# Sensor_Schematic.net
KiCad netlist of a schematic drawn in Altium Designer
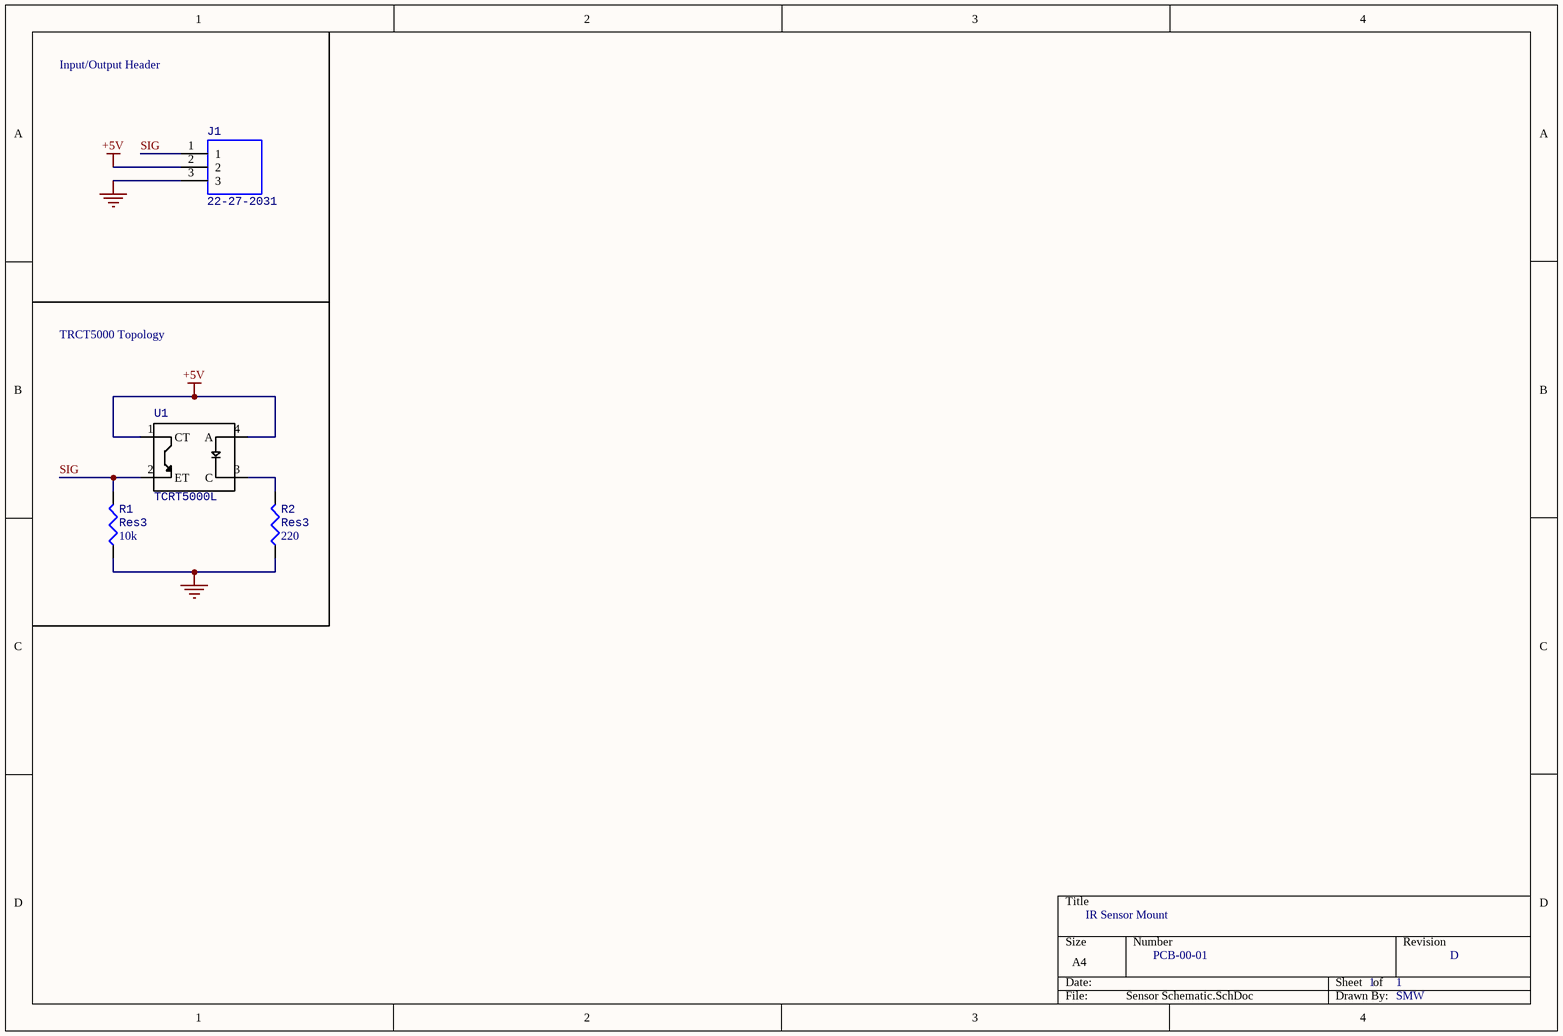
[diagram p0: Sensor Schematic.SchDoc]

(export (version "E")
  (design (tool "Eeschema 10.0.6"))
  (components
    (comp (ref "J1")
      (value "22-27-2031")
      (footprint "SHDR3W64P0X254_1X3_762X580X1170P")
      (fields (field (name "RS PART NUMBER") "1707102"))
      (libsource (lib "22-27-2031") (part "22-27-2031"))
    )
    (comp (ref "R1")
      (value "Res3")
      (footprint "J1-0603")
      (description "Resistor")
      (fields (field (name "ALTIUM_VALUE") "10k") (field (name "PUBLISHER") "Altium Limited"))
      (libsource (lib "Miscellaneous Devices") (part "Res3"))
    )
    (comp (ref "R2")
      (value "Res3")
      (footprint "J1-0603")
      (description "Resistor")
      (fields (field (name "ALTIUM_VALUE") "220") (field (name "PUBLISHER") "Altium Limited"))
      (libsource (lib "Miscellaneous Devices") (part "Res3"))
    )
    (comp (ref "U1")
      (value "TCRT5000L")
      (footprint "XDCR_TCRT5000L")
      (description "TCRT5000 Series 940 nm 100 mA 60 mA Transistor Output Reflective Optical Sensor")
      (fields (field (name "MF") "Vishay Semiconductor"))
      (libsource (lib "TCRT5000L") (part "TCRT5000L"))
    )
  )
  (nets
    (net (code "1") (name "+5V") (class "Default")
      (node (ref "J1") (pin "2") (pinfunction "2_2") (pintype "passive"))
      (node (ref "U1") (pin "1") (pinfunction "CT_1") (pintype "passive"))
      (node (ref "U1") (pin "4") (pinfunction "A_4") (pintype "passive"))
    )
    (net (code "2") (name "/SIG") (class "Default")
      (node (ref "J1") (pin "1") (pinfunction "1_1") (pintype "passive"))
      (node (ref "R1") (pin "2") (pinfunction "2_2") (pintype "passive"))
      (node (ref "U1") (pin "2") (pinfunction "ET_2") (pintype "passive"))
    )
    (net (code "3") (name "GND") (class "Default")
      (node (ref "J1") (pin "3") (pinfunction "3_3") (pintype "passive"))
      (node (ref "R1") (pin "1") (pinfunction "1_1") (pintype "passive"))
      (node (ref "R2") (pin "1") (pinfunction "1_1") (pintype "passive"))
    )
    (net (code "4") (name "Net-(U1-C)") (class "Default")
      (node (ref "R2") (pin "2") (pinfunction "2_2") (pintype "passive"))
      (node (ref "U1") (pin "3") (pinfunction "C_3") (pintype "passive"))
    )
  )
)
